# BLUE_TO_IDC_Sheet1.net
KiCad netlist of a schematic drawn in Altium Designer
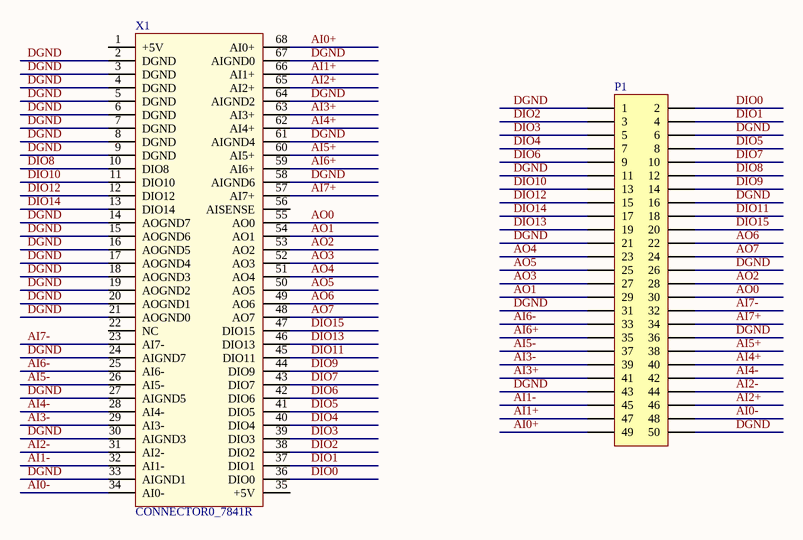
[diagram p0: BLUE_TO_IDC_Sheet1.SchDoc]

(export (version "E")
  (design (tool "Eeschema 10.0.6"))
  (components
    (comp (ref "P1")
      (value "Header 25X2")
      (footprint "HDR2X25")
      (description "Header, 25-Pin, Dual row")
      (fields (field (name "PUBLISHER") "Altium Limited"))
      (libsource (lib "Miscellaneous Connectors") (part "Header 25X2"))
    )
    (comp (ref "X1")
      (value "CONNECTOR0_7841R")
      (footprint "CONNECTOR0_7841R")
      (libsource (lib "VPL") (part "CONNECTOR0_7841R"))
    )
  )
  (nets
    (net (code "1") (name "/AI0+") (class "Default")
      (node (ref "P1") (pin "49") (pinfunction "49_49") (pintype "passive"))
      (node (ref "X1") (pin "68") (pinfunction "AI0+_68") (pintype "passive"))
    )
    (net (code "2") (name "/AI0-") (class "Default")
      (node (ref "P1") (pin "48") (pinfunction "48_48") (pintype "passive"))
      (node (ref "X1") (pin "34") (pinfunction "AI0-_34") (pintype "passive"))
    )
    (net (code "3") (name "/AI1+") (class "Default")
      (node (ref "P1") (pin "47") (pinfunction "47_47") (pintype "passive"))
      (node (ref "X1") (pin "66") (pinfunction "AI1+_66") (pintype "passive"))
    )
    (net (code "4") (name "/AI1-") (class "Default")
      (node (ref "P1") (pin "45") (pinfunction "45_45") (pintype "passive"))
      (node (ref "X1") (pin "32") (pinfunction "AI1-_32") (pintype "passive"))
    )
    (net (code "5") (name "/AI2+") (class "Default")
      (node (ref "P1") (pin "46") (pinfunction "46_46") (pintype "passive"))
      (node (ref "X1") (pin "65") (pinfunction "AI2+_65") (pintype "passive"))
    )
    (net (code "6") (name "/AI2-") (class "Default")
      (node (ref "P1") (pin "44") (pinfunction "44_44") (pintype "passive"))
      (node (ref "X1") (pin "31") (pinfunction "AI2-_31") (pintype "passive"))
    )
    (net (code "7") (name "/AI3+") (class "Default")
      (node (ref "P1") (pin "41") (pinfunction "41_41") (pintype "passive"))
      (node (ref "X1") (pin "63") (pinfunction "AI3+_63") (pintype "passive"))
    )
    (net (code "8") (name "/AI3-") (class "Default")
      (node (ref "P1") (pin "39") (pinfunction "39_39") (pintype "passive"))
      (node (ref "X1") (pin "29") (pinfunction "AI3-_29") (pintype "passive"))
    )
    (net (code "9") (name "/AI4+") (class "Default")
      (node (ref "P1") (pin "40") (pinfunction "40_40") (pintype "passive"))
      (node (ref "X1") (pin "62") (pinfunction "AI4+_62") (pintype "passive"))
    )
    (net (code "10") (name "/AI4-") (class "Default")
      (node (ref "P1") (pin "42") (pinfunction "42_42") (pintype "passive"))
      (node (ref "X1") (pin "28") (pinfunction "AI4-_28") (pintype "passive"))
    )
    (net (code "11") (name "/AI5+") (class "Default")
      (node (ref "P1") (pin "38") (pinfunction "38_38") (pintype "passive"))
      (node (ref "X1") (pin "60") (pinfunction "AI5+_60") (pintype "passive"))
    )
    (net (code "12") (name "/AI5-") (class "Default")
      (node (ref "P1") (pin "37") (pinfunction "37_37") (pintype "passive"))
      (node (ref "X1") (pin "26") (pinfunction "AI5-_26") (pintype "passive"))
    )
    (net (code "13") (name "/AI6+") (class "Default")
      (node (ref "P1") (pin "35") (pinfunction "35_35") (pintype "passive"))
      (node (ref "X1") (pin "59") (pinfunction "AI6+_59") (pintype "passive"))
    )
    (net (code "14") (name "/AI6-") (class "Default")
      (node (ref "P1") (pin "33") (pinfunction "33_33") (pintype "passive"))
      (node (ref "X1") (pin "25") (pinfunction "AI6-_25") (pintype "passive"))
    )
    (net (code "15") (name "/AI7+") (class "Default")
      (node (ref "P1") (pin "34") (pinfunction "34_34") (pintype "passive"))
      (node (ref "X1") (pin "57") (pinfunction "AI7+_57") (pintype "passive"))
    )
    (net (code "16") (name "/AI7-") (class "Default")
      (node (ref "P1") (pin "32") (pinfunction "32_32") (pintype "passive"))
      (node (ref "X1") (pin "23") (pinfunction "AI7-_23") (pintype "passive"))
    )
    (net (code "17") (name "/AO0") (class "Default")
      (node (ref "P1") (pin "30") (pinfunction "30_30") (pintype "passive"))
      (node (ref "X1") (pin "55") (pinfunction "AO0_55") (pintype "passive"))
    )
    (net (code "18") (name "/AO1") (class "Default")
      (node (ref "P1") (pin "29") (pinfunction "29_29") (pintype "passive"))
      (node (ref "X1") (pin "54") (pinfunction "AO1_54") (pintype "passive"))
    )
    (net (code "19") (name "/AO2") (class "Default")
      (node (ref "P1") (pin "28") (pinfunction "28_28") (pintype "passive"))
      (node (ref "X1") (pin "53") (pinfunction "AO2_53") (pintype "passive"))
    )
    (net (code "20") (name "/AO3") (class "Default")
      (node (ref "P1") (pin "27") (pinfunction "27_27") (pintype "passive"))
      (node (ref "X1") (pin "52") (pinfunction "AO3_52") (pintype "passive"))
    )
    (net (code "21") (name "/AO4") (class "Default")
      (node (ref "P1") (pin "23") (pinfunction "23_23") (pintype "passive"))
      (node (ref "X1") (pin "51") (pinfunction "AO4_51") (pintype "passive"))
    )
    (net (code "22") (name "/AO5") (class "Default")
      (node (ref "P1") (pin "25") (pinfunction "25_25") (pintype "passive"))
      (node (ref "X1") (pin "50") (pinfunction "AO5_50") (pintype "passive"))
    )
    (net (code "23") (name "/AO6") (class "Default")
      (node (ref "P1") (pin "22") (pinfunction "22_22") (pintype "passive"))
      (node (ref "X1") (pin "49") (pinfunction "AO6_49") (pintype "passive"))
    )
    (net (code "24") (name "/AO7") (class "Default")
      (node (ref "P1") (pin "24") (pinfunction "24_24") (pintype "passive"))
      (node (ref "X1") (pin "48") (pinfunction "AO7_48") (pintype "passive"))
    )
    (net (code "25") (name "/DGND") (class "Default")
      (node (ref "P1") (pin "1") (pinfunction "1_1") (pintype "passive"))
      (node (ref "P1") (pin "11") (pinfunction "11_11") (pintype "passive"))
      (node (ref "P1") (pin "16") (pinfunction "16_16") (pintype "passive"))
      (node (ref "P1") (pin "21") (pinfunction "21_21") (pintype "passive"))
      (node (ref "P1") (pin "26") (pinfunction "26_26") (pintype "passive"))
      (node (ref "P1") (pin "31") (pinfunction "31_31") (pintype "passive"))
      (node (ref "P1") (pin "36") (pinfunction "36_36") (pintype "passive"))
      (node (ref "P1") (pin "43") (pinfunction "43_43") (pintype "passive"))
      (node (ref "P1") (pin "50") (pinfunction "50_50") (pintype "passive"))
      (node (ref "P1") (pin "6") (pinfunction "6_6") (pintype "passive"))
      (node (ref "X1") (pin "14") (pinfunction "AOGND7_14") (pintype "passive"))
      (node (ref "X1") (pin "15") (pinfunction "AOGND6_15") (pintype "passive"))
      (node (ref "X1") (pin "16") (pinfunction "AOGND5_16") (pintype "passive"))
      (node (ref "X1") (pin "17") (pinfunction "AOGND4_17") (pintype "passive"))
      (node (ref "X1") (pin "18") (pinfunction "AOGND3_18") (pintype "passive"))
      (node (ref "X1") (pin "19") (pinfunction "AOGND2_19") (pintype "passive"))
      (node (ref "X1") (pin "2") (pinfunction "DGND_2") (pintype "passive"))
      (node (ref "X1") (pin "20") (pinfunction "AOGND1_20") (pintype "passive"))
      (node (ref "X1") (pin "21") (pinfunction "AOGND0_21") (pintype "passive"))
      (node (ref "X1") (pin "24") (pinfunction "AIGND7_24") (pintype "passive"))
      (node (ref "X1") (pin "27") (pinfunction "AIGND5_27") (pintype "passive"))
      (node (ref "X1") (pin "3") (pinfunction "DGND_3") (pintype "passive"))
      (node (ref "X1") (pin "30") (pinfunction "AIGND3_30") (pintype "passive"))
      (node (ref "X1") (pin "33") (pinfunction "AIGND1_33") (pintype "passive"))
      (node (ref "X1") (pin "4") (pinfunction "DGND_4") (pintype "passive"))
      (node (ref "X1") (pin "5") (pinfunction "DGND_5") (pintype "passive"))
      (node (ref "X1") (pin "58") (pinfunction "AIGND6_58") (pintype "passive"))
      (node (ref "X1") (pin "6") (pinfunction "DGND_6") (pintype "passive"))
      (node (ref "X1") (pin "61") (pinfunction "AIGND4_61") (pintype "passive"))
      (node (ref "X1") (pin "64") (pinfunction "AIGND2_64") (pintype "passive"))
      (node (ref "X1") (pin "67") (pinfunction "AIGND0_67") (pintype "passive"))
      (node (ref "X1") (pin "7") (pinfunction "DGND_7") (pintype "passive"))
      (node (ref "X1") (pin "8") (pinfunction "DGND_8") (pintype "passive"))
      (node (ref "X1") (pin "9") (pinfunction "DGND_9") (pintype "passive"))
    )
    (net (code "26") (name "/DIO0") (class "Default")
      (node (ref "P1") (pin "2") (pinfunction "2_2") (pintype "passive"))
      (node (ref "X1") (pin "36") (pinfunction "DIO0_36") (pintype "passive"))
    )
    (net (code "27") (name "/DIO1") (class "Default")
      (node (ref "P1") (pin "4") (pinfunction "4_4") (pintype "passive"))
      (node (ref "X1") (pin "37") (pinfunction "DIO1_37") (pintype "passive"))
    )
    (net (code "28") (name "/DIO2") (class "Default")
      (node (ref "P1") (pin "3") (pinfunction "3_3") (pintype "passive"))
      (node (ref "X1") (pin "38") (pinfunction "DIO2_38") (pintype "passive"))
    )
    (net (code "29") (name "/DIO3") (class "Default")
      (node (ref "P1") (pin "5") (pinfunction "5_5") (pintype "passive"))
      (node (ref "X1") (pin "39") (pinfunction "DIO3_39") (pintype "passive"))
    )
    (net (code "30") (name "/DIO4") (class "Default")
      (node (ref "P1") (pin "7") (pinfunction "7_7") (pintype "passive"))
      (node (ref "X1") (pin "40") (pinfunction "DIO4_40") (pintype "passive"))
    )
    (net (code "31") (name "/DIO5") (class "Default")
      (node (ref "P1") (pin "8") (pinfunction "8_8") (pintype "passive"))
      (node (ref "X1") (pin "41") (pinfunction "DIO5_41") (pintype "passive"))
    )
    (net (code "32") (name "/DIO6") (class "Default")
      (node (ref "P1") (pin "9") (pinfunction "9_9") (pintype "passive"))
      (node (ref "X1") (pin "42") (pinfunction "DIO6_42") (pintype "passive"))
    )
    (net (code "33") (name "/DIO7") (class "Default")
      (node (ref "P1") (pin "10") (pinfunction "10_10") (pintype "passive"))
      (node (ref "X1") (pin "43") (pinfunction "DIO7_43") (pintype "passive"))
    )
    (net (code "34") (name "/DIO8") (class "Default")
      (node (ref "P1") (pin "12") (pinfunction "12_12") (pintype "passive"))
      (node (ref "X1") (pin "10") (pinfunction "DIO8_10") (pintype "passive"))
    )
    (net (code "35") (name "/DIO9") (class "Default")
      (node (ref "P1") (pin "14") (pinfunction "14_14") (pintype "passive"))
      (node (ref "X1") (pin "44") (pinfunction "DIO9_44") (pintype "passive"))
    )
    (net (code "36") (name "/DIO10") (class "Default")
      (node (ref "P1") (pin "13") (pinfunction "13_13") (pintype "passive"))
      (node (ref "X1") (pin "11") (pinfunction "DIO10_11") (pintype "passive"))
    )
    (net (code "37") (name "/DIO11") (class "Default")
      (node (ref "P1") (pin "18") (pinfunction "18_18") (pintype "passive"))
      (node (ref "X1") (pin "45") (pinfunction "DIO11_45") (pintype "passive"))
    )
    (net (code "38") (name "/DIO12") (class "Default")
      (node (ref "P1") (pin "15") (pinfunction "15_15") (pintype "passive"))
      (node (ref "X1") (pin "12") (pinfunction "DIO12_12") (pintype "passive"))
    )
    (net (code "39") (name "/DIO13") (class "Default")
      (node (ref "P1") (pin "19") (pinfunction "19_19") (pintype "passive"))
      (node (ref "X1") (pin "46") (pinfunction "DIO13_46") (pintype "passive"))
    )
    (net (code "40") (name "/DIO14") (class "Default")
      (node (ref "P1") (pin "17") (pinfunction "17_17") (pintype "passive"))
      (node (ref "X1") (pin "13") (pinfunction "DIO14_13") (pintype "passive"))
    )
    (net (code "41") (name "/DIO15") (class "Default")
      (node (ref "P1") (pin "20") (pinfunction "20_20") (pintype "passive"))
      (node (ref "X1") (pin "47") (pinfunction "DIO15_47") (pintype "passive"))
    )
    (net (code "42") (name "unconnected-(X1-+5V-Pad1)") (class "Default")
      (node (ref "X1") (pin "1") (pinfunction "+5V_1") (pintype "passive"))
    )
    (net (code "43") (name "unconnected-(X1-+5V-Pad35)") (class "Default")
      (node (ref "X1") (pin "35") (pinfunction "+5V_35") (pintype "passive"))
    )
    (net (code "44") (name "unconnected-(X1-AISENSE-Pad56)") (class "Default")
      (node (ref "X1") (pin "56") (pinfunction "AISENSE_56") (pintype "passive"))
    )
    (net (code "45") (name "unconnected-(X1-NC-Pad22)") (class "Default")
      (node (ref "X1") (pin "22") (pinfunction "NC_22") (pintype "passive"))
    )
  )
)
